# IR_Sensor.net
KiCad netlist of a schematic drawn in EAGLE
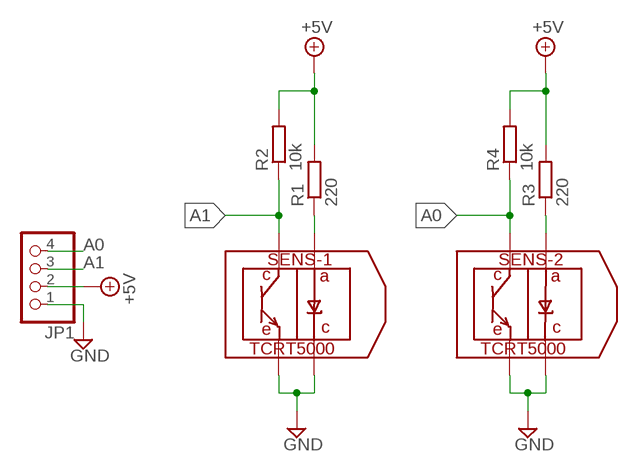
[diagram p0: schematic, sheet 1]

(export (version "E")
  (design (tool "Eeschema 10.0.6"))
  (components
    (comp (ref "JP1")
      (value "PINHD-1X4/90")
      (footprint "eagle-import:1X04_90")
      (libsource (lib "eagle-import") (part "PINHD-1X4/90"))
    )
    (comp (ref "R1")
      (value "220")
      (footprint "eagle-import:0204_7")
      (libsource (lib "eagle-import") (part "R-EU_0204/7"))
    )
    (comp (ref "R2")
      (value "10k")
      (footprint "eagle-import:0204_7")
      (libsource (lib "eagle-import") (part "R-EU_0204/7"))
    )
    (comp (ref "R3")
      (value "220")
      (footprint "eagle-import:0204_7")
      (libsource (lib "eagle-import") (part "R-EU_0204/7"))
    )
    (comp (ref "R4")
      (value "10k")
      (footprint "eagle-import:0204_7")
      (libsource (lib "eagle-import") (part "R-EU_0204/7"))
    )
    (comp (ref "SENS-1")
      (value "TCRT5000")
      (footprint "eagle-import:5000")
      (libsource (lib "eagle-import") (part "TCRT5000"))
    )
    (comp (ref "SENS-2")
      (value "TCRT5000")
      (footprint "eagle-import:5000")
      (libsource (lib "eagle-import") (part "TCRT5000"))
    )
  )
  (nets
    (net (code "1") (name "+5V") (class "Default")
      (node (ref "JP1") (pin "2") (pinfunction "2_2") (pintype "passive"))
      (node (ref "R1") (pin "2") (pinfunction "2_2") (pintype "passive"))
      (node (ref "R2") (pin "2") (pinfunction "2_2") (pintype "passive"))
      (node (ref "R3") (pin "2") (pinfunction "2_2") (pintype "passive"))
      (node (ref "R4") (pin "2") (pinfunction "2_2") (pintype "passive"))
    )
    (net (code "2") (name "A0") (class "Default")
      (node (ref "JP1") (pin "4") (pinfunction "4_4") (pintype "passive"))
      (node (ref "R4") (pin "1") (pinfunction "1_1") (pintype "passive"))
      (node (ref "SENS-2") (pin "P$1") (pinfunction "P$1_P$1") (pintype "passive"))
    )
    (net (code "3") (name "A1") (class "Default")
      (node (ref "JP1") (pin "3") (pinfunction "3_3") (pintype "passive"))
      (node (ref "R2") (pin "1") (pinfunction "1_1") (pintype "passive"))
      (node (ref "SENS-1") (pin "P$1") (pinfunction "P$1_P$1") (pintype "passive"))
    )
    (net (code "4") (name "GND") (class "Default")
      (node (ref "JP1") (pin "1") (pinfunction "1_1") (pintype "passive"))
      (node (ref "SENS-1") (pin "P$2") (pinfunction "P$2_P$2") (pintype "passive"))
      (node (ref "SENS-1") (pin "P$4") (pinfunction "P$4_P$4") (pintype "passive"))
      (node (ref "SENS-2") (pin "P$2") (pinfunction "P$2_P$2") (pintype "passive"))
      (node (ref "SENS-2") (pin "P$4") (pinfunction "P$4_P$4") (pintype "passive"))
    )
    (net (code "5") (name "Net-(R1-Pad1)") (class "Default")
      (node (ref "R1") (pin "1") (pinfunction "1_1") (pintype "passive"))
      (node (ref "SENS-1") (pin "P$3") (pinfunction "P$3_P$3") (pintype "passive"))
    )
    (net (code "6") (name "Net-(R3-Pad1)") (class "Default")
      (node (ref "R3") (pin "1") (pinfunction "1_1") (pintype "passive"))
      (node (ref "SENS-2") (pin "P$3") (pinfunction "P$3_P$3") (pintype "passive"))
    )
  )
)
